# PlantowerSPS.net
KiCad netlist of a schematic drawn in EAGLE
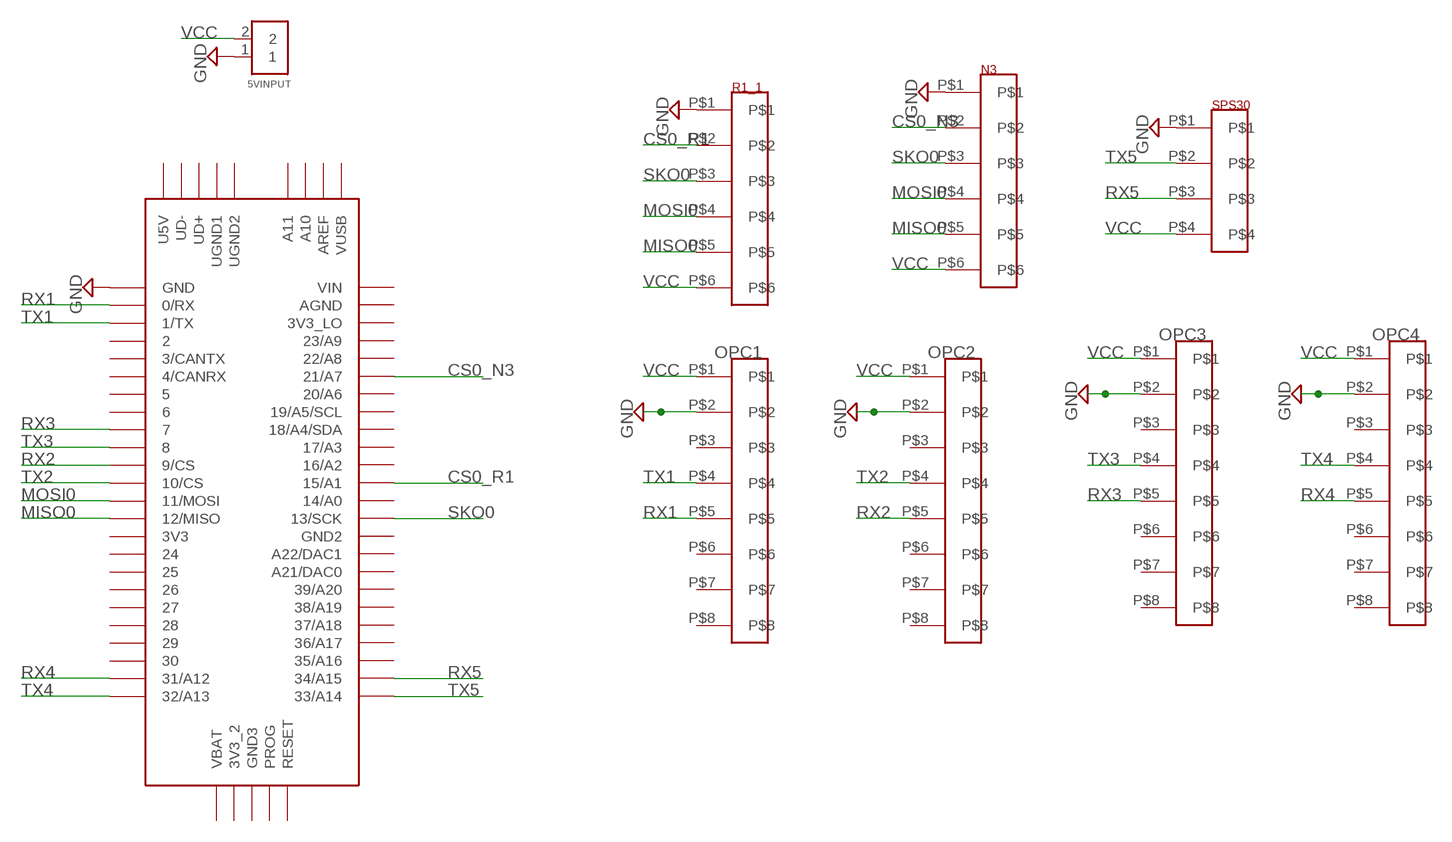
[diagram p0: schematic, sheet 1]

(export (version "E")
  (design (tool "Eeschema 10.0.6"))
  (components
    (comp (ref "5VINPUT")
      (value "2PIN_TERMINAL_BLOCK")
      (footprint "eagle-import:2PIN_TERMINAL_BLOCK")
      (fields
        (field (name "COMMENT") "282834-2")
        (field (name "DIGI-KEY_PART_NUMBER") "A98333-ND")
        (field (name "MF") "TE Connectivity")
      )
      (libsource (lib "eagle-import") (part "2PIN_TERMINAL_BLOCK"))
    )
    (comp (ref "N3")
      (value "6PINHEADER")
      (footprint "eagle-import:6PINHEADER")
      (libsource (lib "eagle-import") (part "6PINHEADER"))
    )
    (comp (ref "OPC1")
      (value "8PINHEADER")
      (footprint "eagle-import:8PINHEADER")
      (libsource (lib "eagle-import") (part "8PINHEADER"))
    )
    (comp (ref "OPC2")
      (value "8PINHEADER")
      (footprint "eagle-import:8PINHEADER")
      (libsource (lib "eagle-import") (part "8PINHEADER"))
    )
    (comp (ref "OPC3")
      (value "8PINHEADER")
      (footprint "eagle-import:8PINHEADER")
      (libsource (lib "eagle-import") (part "8PINHEADER"))
    )
    (comp (ref "OPC4")
      (value "8PINHEADER")
      (footprint "eagle-import:8PINHEADER")
      (libsource (lib "eagle-import") (part "8PINHEADER"))
    )
    (comp (ref "R1_1")
      (value "6PINHEADER")
      (footprint "eagle-import:6PINHEADER")
      (libsource (lib "eagle-import") (part "6PINHEADER"))
    )
    (comp (ref "SPS30")
      (value "4PINHEADER")
      (footprint "eagle-import:4PINHEADER")
      (libsource (lib "eagle-import") (part "4PINHEADER"))
    )
    (comp (ref "U$1")
      (value "TEENSY_3.5/3.6")
      (footprint "eagle-import:TEENSY_3.5_3.6")
      (libsource (lib "eagle-import") (part "TEENSY_3.5/3.6"))
    )
  )
  (nets
    (net (code "1") (name "/CS0_N3") (class "Default")
      (node (ref "N3") (pin "P$2") (pinfunction "P$2_P$2") (pintype "bidirectional"))
      (node (ref "U$1") (pin "21/A7") (pinfunction "21/A7_21/A7") (pintype "bidirectional"))
    )
    (net (code "2") (name "/CS0_R1") (class "Default")
      (node (ref "R1_1") (pin "P$2") (pinfunction "P$2_P$2") (pintype "bidirectional"))
      (node (ref "U$1") (pin "15/A1") (pinfunction "15/A1_15/A1") (pintype "bidirectional"))
    )
    (net (code "3") (name "/MISO0") (class "Default")
      (node (ref "N3") (pin "P$5") (pinfunction "P$5_P$5") (pintype "bidirectional"))
      (node (ref "R1_1") (pin "P$5") (pinfunction "P$5_P$5") (pintype "bidirectional"))
      (node (ref "U$1") (pin "12/MISO") (pinfunction "12/MISO_12/MISO") (pintype "bidirectional"))
    )
    (net (code "4") (name "/MOSI0") (class "Default")
      (node (ref "N3") (pin "P$4") (pinfunction "P$4_P$4") (pintype "bidirectional"))
      (node (ref "R1_1") (pin "P$4") (pinfunction "P$4_P$4") (pintype "bidirectional"))
      (node (ref "U$1") (pin "11/MOSI") (pinfunction "11/MOSI_11/MOSI") (pintype "bidirectional"))
    )
    (net (code "5") (name "/RX1") (class "Default")
      (node (ref "OPC1") (pin "P$5") (pinfunction "P$5_P$5") (pintype "bidirectional"))
      (node (ref "U$1") (pin "0/RX") (pinfunction "0/RX_0/RX") (pintype "bidirectional"))
    )
    (net (code "6") (name "/RX2") (class "Default")
      (node (ref "OPC2") (pin "P$5") (pinfunction "P$5_P$5") (pintype "bidirectional"))
      (node (ref "U$1") (pin "9/CS") (pinfunction "9/CS_9/CS") (pintype "bidirectional"))
    )
    (net (code "7") (name "/RX3") (class "Default")
      (node (ref "OPC3") (pin "P$5") (pinfunction "P$5_P$5") (pintype "bidirectional"))
      (node (ref "U$1") (pin "7") (pinfunction "7_7") (pintype "bidirectional"))
    )
    (net (code "8") (name "/RX4") (class "Default")
      (node (ref "OPC4") (pin "P$5") (pinfunction "P$5_P$5") (pintype "bidirectional"))
      (node (ref "U$1") (pin "31/A12") (pinfunction "31/A12_31/A12") (pintype "bidirectional"))
    )
    (net (code "9") (name "/RX5") (class "Default")
      (node (ref "SPS30") (pin "P$3") (pinfunction "P$3_P$3") (pintype "bidirectional"))
      (node (ref "U$1") (pin "34/A15") (pinfunction "34/A15_34/A15") (pintype "bidirectional"))
    )
    (net (code "10") (name "/SKO0") (class "Default")
      (node (ref "N3") (pin "P$3") (pinfunction "P$3_P$3") (pintype "bidirectional"))
      (node (ref "R1_1") (pin "P$3") (pinfunction "P$3_P$3") (pintype "bidirectional"))
      (node (ref "U$1") (pin "13/SCK") (pinfunction "13/SCK_13/SCK") (pintype "bidirectional"))
    )
    (net (code "11") (name "/TX1") (class "Default")
      (node (ref "OPC1") (pin "P$4") (pinfunction "P$4_P$4") (pintype "bidirectional"))
      (node (ref "U$1") (pin "1/TX") (pinfunction "1/TX_1/TX") (pintype "bidirectional"))
    )
    (net (code "12") (name "/TX2") (class "Default")
      (node (ref "OPC2") (pin "P$4") (pinfunction "P$4_P$4") (pintype "bidirectional"))
      (node (ref "U$1") (pin "10/CS") (pinfunction "10/CS_10/CS") (pintype "bidirectional"))
    )
    (net (code "13") (name "/TX3") (class "Default")
      (node (ref "OPC3") (pin "P$4") (pinfunction "P$4_P$4") (pintype "bidirectional"))
      (node (ref "U$1") (pin "8") (pinfunction "8_8") (pintype "bidirectional"))
    )
    (net (code "14") (name "/TX4") (class "Default")
      (node (ref "OPC4") (pin "P$4") (pinfunction "P$4_P$4") (pintype "bidirectional"))
      (node (ref "U$1") (pin "32/A13") (pinfunction "32/A13_32/A13") (pintype "bidirectional"))
    )
    (net (code "15") (name "/TX5") (class "Default")
      (node (ref "SPS30") (pin "P$2") (pinfunction "P$2_P$2") (pintype "bidirectional"))
      (node (ref "U$1") (pin "33/A14") (pinfunction "33/A14_33/A14") (pintype "bidirectional"))
    )
    (net (code "16") (name "/VCC") (class "Default")
      (node (ref "5VINPUT") (pin "2") (pinfunction "2_2") (pintype "passive"))
      (node (ref "N3") (pin "P$6") (pinfunction "P$6_P$6") (pintype "bidirectional"))
      (node (ref "OPC1") (pin "P$1") (pinfunction "P$1_P$1") (pintype "bidirectional"))
      (node (ref "OPC2") (pin "P$1") (pinfunction "P$1_P$1") (pintype "bidirectional"))
      (node (ref "OPC3") (pin "P$1") (pinfunction "P$1_P$1") (pintype "bidirectional"))
      (node (ref "OPC4") (pin "P$1") (pinfunction "P$1_P$1") (pintype "bidirectional"))
      (node (ref "R1_1") (pin "P$6") (pinfunction "P$6_P$6") (pintype "bidirectional"))
      (node (ref "SPS30") (pin "P$4") (pinfunction "P$4_P$4") (pintype "bidirectional"))
    )
    (net (code "17") (name "GND") (class "Default")
      (node (ref "5VINPUT") (pin "1") (pinfunction "1_1") (pintype "passive"))
      (node (ref "N3") (pin "P$1") (pinfunction "P$1_P$1") (pintype "bidirectional"))
      (node (ref "OPC1") (pin "P$2") (pinfunction "P$2_P$2") (pintype "bidirectional"))
      (node (ref "OPC2") (pin "P$2") (pinfunction "P$2_P$2") (pintype "bidirectional"))
      (node (ref "OPC3") (pin "P$2") (pinfunction "P$2_P$2") (pintype "bidirectional"))
      (node (ref "OPC4") (pin "P$2") (pinfunction "P$2_P$2") (pintype "bidirectional"))
      (node (ref "R1_1") (pin "P$1") (pinfunction "P$1_P$1") (pintype "bidirectional"))
      (node (ref "SPS30") (pin "P$1") (pinfunction "P$1_P$1") (pintype "bidirectional"))
      (node (ref "U$1") (pin "GND") (pinfunction "GND_GND") (pintype "bidirectional"))
    )
    (net (code "18") (name "unconnected-(OPC1-PadP$3)") (class "Default")
      (node (ref "OPC1") (pin "P$3") (pinfunction "P$3_P$3") (pintype "bidirectional"))
    )
    (net (code "19") (name "unconnected-(OPC1-PadP$6)") (class "Default")
      (node (ref "OPC1") (pin "P$6") (pinfunction "P$6_P$6") (pintype "bidirectional"))
    )
    (net (code "20") (name "unconnected-(OPC1-PadP$7)") (class "Default")
      (node (ref "OPC1") (pin "P$7") (pinfunction "P$7_P$7") (pintype "bidirectional"))
    )
    (net (code "21") (name "unconnected-(OPC1-PadP$8)") (class "Default")
      (node (ref "OPC1") (pin "P$8") (pinfunction "P$8_P$8") (pintype "bidirectional"))
    )
    (net (code "22") (name "unconnected-(OPC2-PadP$3)") (class "Default")
      (node (ref "OPC2") (pin "P$3") (pinfunction "P$3_P$3") (pintype "bidirectional"))
    )
    (net (code "23") (name "unconnected-(OPC2-PadP$6)") (class "Default")
      (node (ref "OPC2") (pin "P$6") (pinfunction "P$6_P$6") (pintype "bidirectional"))
    )
    (net (code "24") (name "unconnected-(OPC2-PadP$7)") (class "Default")
      (node (ref "OPC2") (pin "P$7") (pinfunction "P$7_P$7") (pintype "bidirectional"))
    )
    (net (code "25") (name "unconnected-(OPC2-PadP$8)") (class "Default")
      (node (ref "OPC2") (pin "P$8") (pinfunction "P$8_P$8") (pintype "bidirectional"))
    )
    (net (code "26") (name "unconnected-(OPC3-PadP$3)") (class "Default")
      (node (ref "OPC3") (pin "P$3") (pinfunction "P$3_P$3") (pintype "bidirectional"))
    )
    (net (code "27") (name "unconnected-(OPC3-PadP$6)") (class "Default")
      (node (ref "OPC3") (pin "P$6") (pinfunction "P$6_P$6") (pintype "bidirectional"))
    )
    (net (code "28") (name "unconnected-(OPC3-PadP$7)") (class "Default")
      (node (ref "OPC3") (pin "P$7") (pinfunction "P$7_P$7") (pintype "bidirectional"))
    )
    (net (code "29") (name "unconnected-(OPC3-PadP$8)") (class "Default")
      (node (ref "OPC3") (pin "P$8") (pinfunction "P$8_P$8") (pintype "bidirectional"))
    )
    (net (code "30") (name "unconnected-(OPC4-PadP$3)") (class "Default")
      (node (ref "OPC4") (pin "P$3") (pinfunction "P$3_P$3") (pintype "bidirectional"))
    )
    (net (code "31") (name "unconnected-(OPC4-PadP$6)") (class "Default")
      (node (ref "OPC4") (pin "P$6") (pinfunction "P$6_P$6") (pintype "bidirectional"))
    )
    (net (code "32") (name "unconnected-(OPC4-PadP$7)") (class "Default")
      (node (ref "OPC4") (pin "P$7") (pinfunction "P$7_P$7") (pintype "bidirectional"))
    )
    (net (code "33") (name "unconnected-(OPC4-PadP$8)") (class "Default")
      (node (ref "OPC4") (pin "P$8") (pinfunction "P$8_P$8") (pintype "bidirectional"))
    )
    (net (code "34") (name "unconnected-(U$1-A21{slash}DAC0-Pad21{slash}DAC0)") (class "Default")
      (node (ref "U$1") (pin "21/DAC0") (pinfunction "A21/DAC0_21/DAC0") (pintype "bidirectional"))
    )
    (net (code "35") (name "unconnected-(U$1-Pad2)") (class "Default")
      (node (ref "U$1") (pin "2") (pinfunction "2_2") (pintype "bidirectional"))
    )
    (net (code "36") (name "unconnected-(U$1-Pad3V3)") (class "Default")
      (node (ref "U$1") (pin "3V3") (pinfunction "3V3_3V3") (pintype "bidirectional"))
    )
    (net (code "37") (name "unconnected-(U$1-Pad3V3_2)") (class "Default")
      (node (ref "U$1") (pin "3V3_2") (pinfunction "3V3_2_3V3_2") (pintype "bidirectional"))
    )
    (net (code "38") (name "unconnected-(U$1-Pad3V3_LO)") (class "Default")
      (node (ref "U$1") (pin "3V3_LO") (pinfunction "3V3_LO_3V3_LO") (pintype "bidirectional"))
    )
    (net (code "39") (name "unconnected-(U$1-Pad3{slash}CANTX)") (class "Default")
      (node (ref "U$1") (pin "3/CANTX") (pinfunction "3/CANTX_3/CANTX") (pintype "bidirectional"))
    )
    (net (code "40") (name "unconnected-(U$1-Pad4{slash}CANRX)") (class "Default")
      (node (ref "U$1") (pin "4/CANRX") (pinfunction "4/CANRX_4/CANRX") (pintype "bidirectional"))
    )
    (net (code "41") (name "unconnected-(U$1-Pad5)") (class "Default")
      (node (ref "U$1") (pin "5") (pinfunction "5_5") (pintype "bidirectional"))
    )
    (net (code "42") (name "unconnected-(U$1-Pad6)") (class "Default")
      (node (ref "U$1") (pin "6") (pinfunction "6_6") (pintype "bidirectional"))
    )
    (net (code "43") (name "unconnected-(U$1-Pad14{slash}A0)") (class "Default")
      (node (ref "U$1") (pin "14/A0") (pinfunction "14/A0_14/A0") (pintype "bidirectional"))
    )
    (net (code "44") (name "unconnected-(U$1-Pad16{slash}A2)") (class "Default")
      (node (ref "U$1") (pin "16/A2") (pinfunction "16/A2_16/A2") (pintype "bidirectional"))
    )
    (net (code "45") (name "unconnected-(U$1-Pad17{slash}A3)") (class "Default")
      (node (ref "U$1") (pin "17/A3") (pinfunction "17/A3_17/A3") (pintype "bidirectional"))
    )
    (net (code "46") (name "unconnected-(U$1-Pad18{slash}A4{slash}SDA)") (class "Default")
      (node (ref "U$1") (pin "18/A4/SDA") (pinfunction "18/A4/SDA_18/A4/SDA") (pintype "bidirectional"))
    )
    (net (code "47") (name "unconnected-(U$1-Pad19{slash}A5{slash}SCL)") (class "Default")
      (node (ref "U$1") (pin "19/A5/SCL") (pinfunction "19/A5/SCL_19/A5/SCL") (pintype "bidirectional"))
    )
    (net (code "48") (name "unconnected-(U$1-Pad20{slash}A6)") (class "Default")
      (node (ref "U$1") (pin "20/A6") (pinfunction "20/A6_20/A6") (pintype "bidirectional"))
    )
    (net (code "49") (name "unconnected-(U$1-Pad22{slash}A8)") (class "Default")
      (node (ref "U$1") (pin "22/A8") (pinfunction "22/A8_22/A8") (pintype "bidirectional"))
    )
    (net (code "50") (name "unconnected-(U$1-Pad23{slash}A9)") (class "Default")
      (node (ref "U$1") (pin "23/A9") (pinfunction "23/A9_23/A9") (pintype "bidirectional"))
    )
    (net (code "51") (name "unconnected-(U$1-Pad24)") (class "Default")
      (node (ref "U$1") (pin "24") (pinfunction "24_24") (pintype "bidirectional"))
    )
    (net (code "52") (name "unconnected-(U$1-Pad25)") (class "Default")
      (node (ref "U$1") (pin "25") (pinfunction "25_25") (pintype "bidirectional"))
    )
    (net (code "53") (name "unconnected-(U$1-Pad26)") (class "Default")
      (node (ref "U$1") (pin "26") (pinfunction "26_26") (pintype "bidirectional"))
    )
    (net (code "54") (name "unconnected-(U$1-Pad27)") (class "Default")
      (node (ref "U$1") (pin "27") (pinfunction "27_27") (pintype "bidirectional"))
    )
    (net (code "55") (name "unconnected-(U$1-Pad28)") (class "Default")
      (node (ref "U$1") (pin "28") (pinfunction "28_28") (pintype "bidirectional"))
    )
    (net (code "56") (name "unconnected-(U$1-Pad29)") (class "Default")
      (node (ref "U$1") (pin "29") (pinfunction "29_29") (pintype "bidirectional"))
    )
    (net (code "57") (name "unconnected-(U$1-Pad30)") (class "Default")
      (node (ref "U$1") (pin "30") (pinfunction "30_30") (pintype "bidirectional"))
    )
    (net (code "58") (name "unconnected-(U$1-Pad35{slash}A16)") (class "Default")
      (node (ref "U$1") (pin "35/A16") (pinfunction "35/A16_35/A16") (pintype "bidirectional"))
    )
    (net (code "59") (name "unconnected-(U$1-Pad36{slash}A17)") (class "Default")
      (node (ref "U$1") (pin "36/A17") (pinfunction "36/A17_36/A17") (pintype "bidirectional"))
    )
    (net (code "60") (name "unconnected-(U$1-Pad37{slash}A18)") (class "Default")
      (node (ref "U$1") (pin "37/A18") (pinfunction "37/A18_37/A18") (pintype "bidirectional"))
    )
    (net (code "61") (name "unconnected-(U$1-Pad38{slash}A19)") (class "Default")
      (node (ref "U$1") (pin "38/A19") (pinfunction "38/A19_38/A19") (pintype "bidirectional"))
    )
    (net (code "62") (name "unconnected-(U$1-Pad39{slash}A20)") (class "Default")
      (node (ref "U$1") (pin "39/A20") (pinfunction "39/A20_39/A20") (pintype "bidirectional"))
    )
    (net (code "63") (name "unconnected-(U$1-PadA10)") (class "Default")
      (node (ref "U$1") (pin "A10") (pinfunction "A10_A10") (pintype "bidirectional"))
    )
    (net (code "64") (name "unconnected-(U$1-PadA11)") (class "Default")
      (node (ref "U$1") (pin "A11") (pinfunction "A11_A11") (pintype "bidirectional"))
    )
    (net (code "65") (name "unconnected-(U$1-PadA22{slash}DAC1)") (class "Default")
      (node (ref "U$1") (pin "A22/DAC1") (pinfunction "A22/DAC1_A22/DAC1") (pintype "bidirectional"))
    )
    (net (code "66") (name "unconnected-(U$1-PadAGND)") (class "Default")
      (node (ref "U$1") (pin "AGND") (pinfunction "AGND_AGND") (pintype "bidirectional"))
    )
    (net (code "67") (name "unconnected-(U$1-PadAREF)") (class "Default")
      (node (ref "U$1") (pin "AREF") (pinfunction "AREF_AREF") (pintype "bidirectional"))
    )
    (net (code "68") (name "unconnected-(U$1-PadGND2)") (class "Default")
      (node (ref "U$1") (pin "GND2") (pinfunction "GND2_GND2") (pintype "bidirectional"))
    )
    (net (code "69") (name "unconnected-(U$1-PadGND3)") (class "Default")
      (node (ref "U$1") (pin "GND3") (pinfunction "GND3_GND3") (pintype "bidirectional"))
    )
    (net (code "70") (name "unconnected-(U$1-PadPROG)") (class "Default")
      (node (ref "U$1") (pin "PROG") (pinfunction "PROG_PROG") (pintype "bidirectional"))
    )
    (net (code "71") (name "unconnected-(U$1-PadRESET)") (class "Default")
      (node (ref "U$1") (pin "RESET") (pinfunction "RESET_RESET") (pintype "bidirectional"))
    )
    (net (code "72") (name "unconnected-(U$1-PadU5V)") (class "Default")
      (node (ref "U$1") (pin "U5V") (pinfunction "U5V_U5V") (pintype "bidirectional"))
    )
    (net (code "73") (name "unconnected-(U$1-PadUD+)") (class "Default")
      (node (ref "U$1") (pin "UD+") (pinfunction "UD+_UD+") (pintype "bidirectional"))
    )
    (net (code "74") (name "unconnected-(U$1-PadUD-)") (class "Default")
      (node (ref "U$1") (pin "UD-") (pinfunction "UD-_UD-") (pintype "bidirectional"))
    )
    (net (code "75") (name "unconnected-(U$1-PadUGND1)") (class "Default")
      (node (ref "U$1") (pin "UGND1") (pinfunction "UGND1_UGND1") (pintype "bidirectional"))
    )
    (net (code "76") (name "unconnected-(U$1-PadUGND2)") (class "Default")
      (node (ref "U$1") (pin "UGND2") (pinfunction "UGND2_UGND2") (pintype "bidirectional"))
    )
    (net (code "77") (name "unconnected-(U$1-PadVBAT)") (class "Default")
      (node (ref "U$1") (pin "VBAT") (pinfunction "VBAT_VBAT") (pintype "bidirectional"))
    )
    (net (code "78") (name "unconnected-(U$1-PadVIN)") (class "Default")
      (node (ref "U$1") (pin "VIN") (pinfunction "VIN_VIN") (pintype "bidirectional"))
    )
    (net (code "79") (name "unconnected-(U$1-PadVUSB)") (class "Default")
      (node (ref "U$1") (pin "VUSB") (pinfunction "VUSB_VUSB") (pintype "bidirectional"))
    )
  )
)
